# power.net
KiCad netlist of a schematic drawn in EAGLE
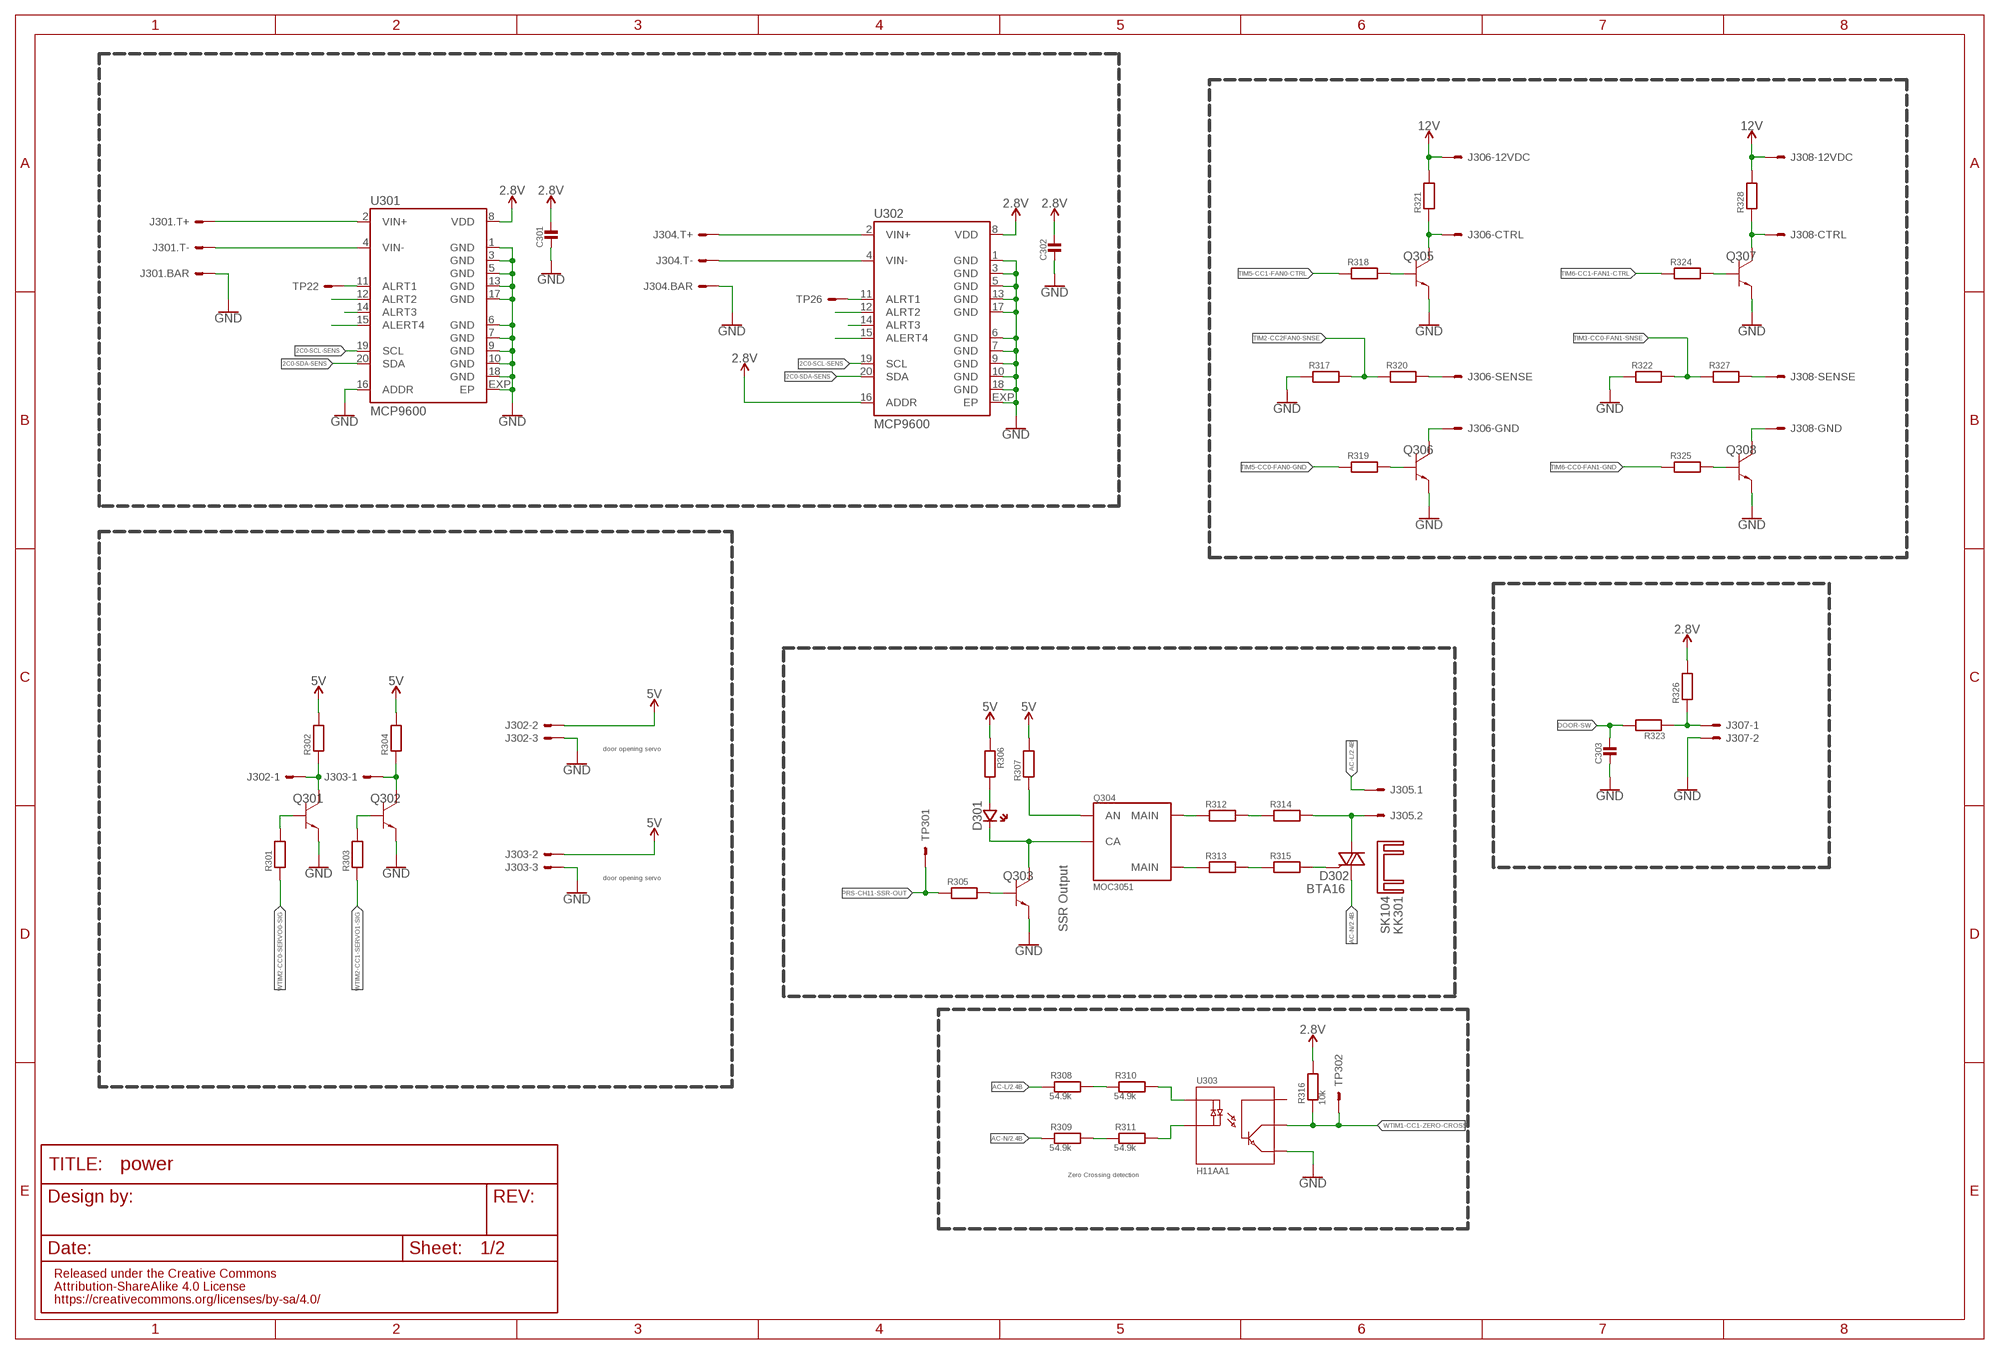
[diagram p0: schematic, sheet 1]
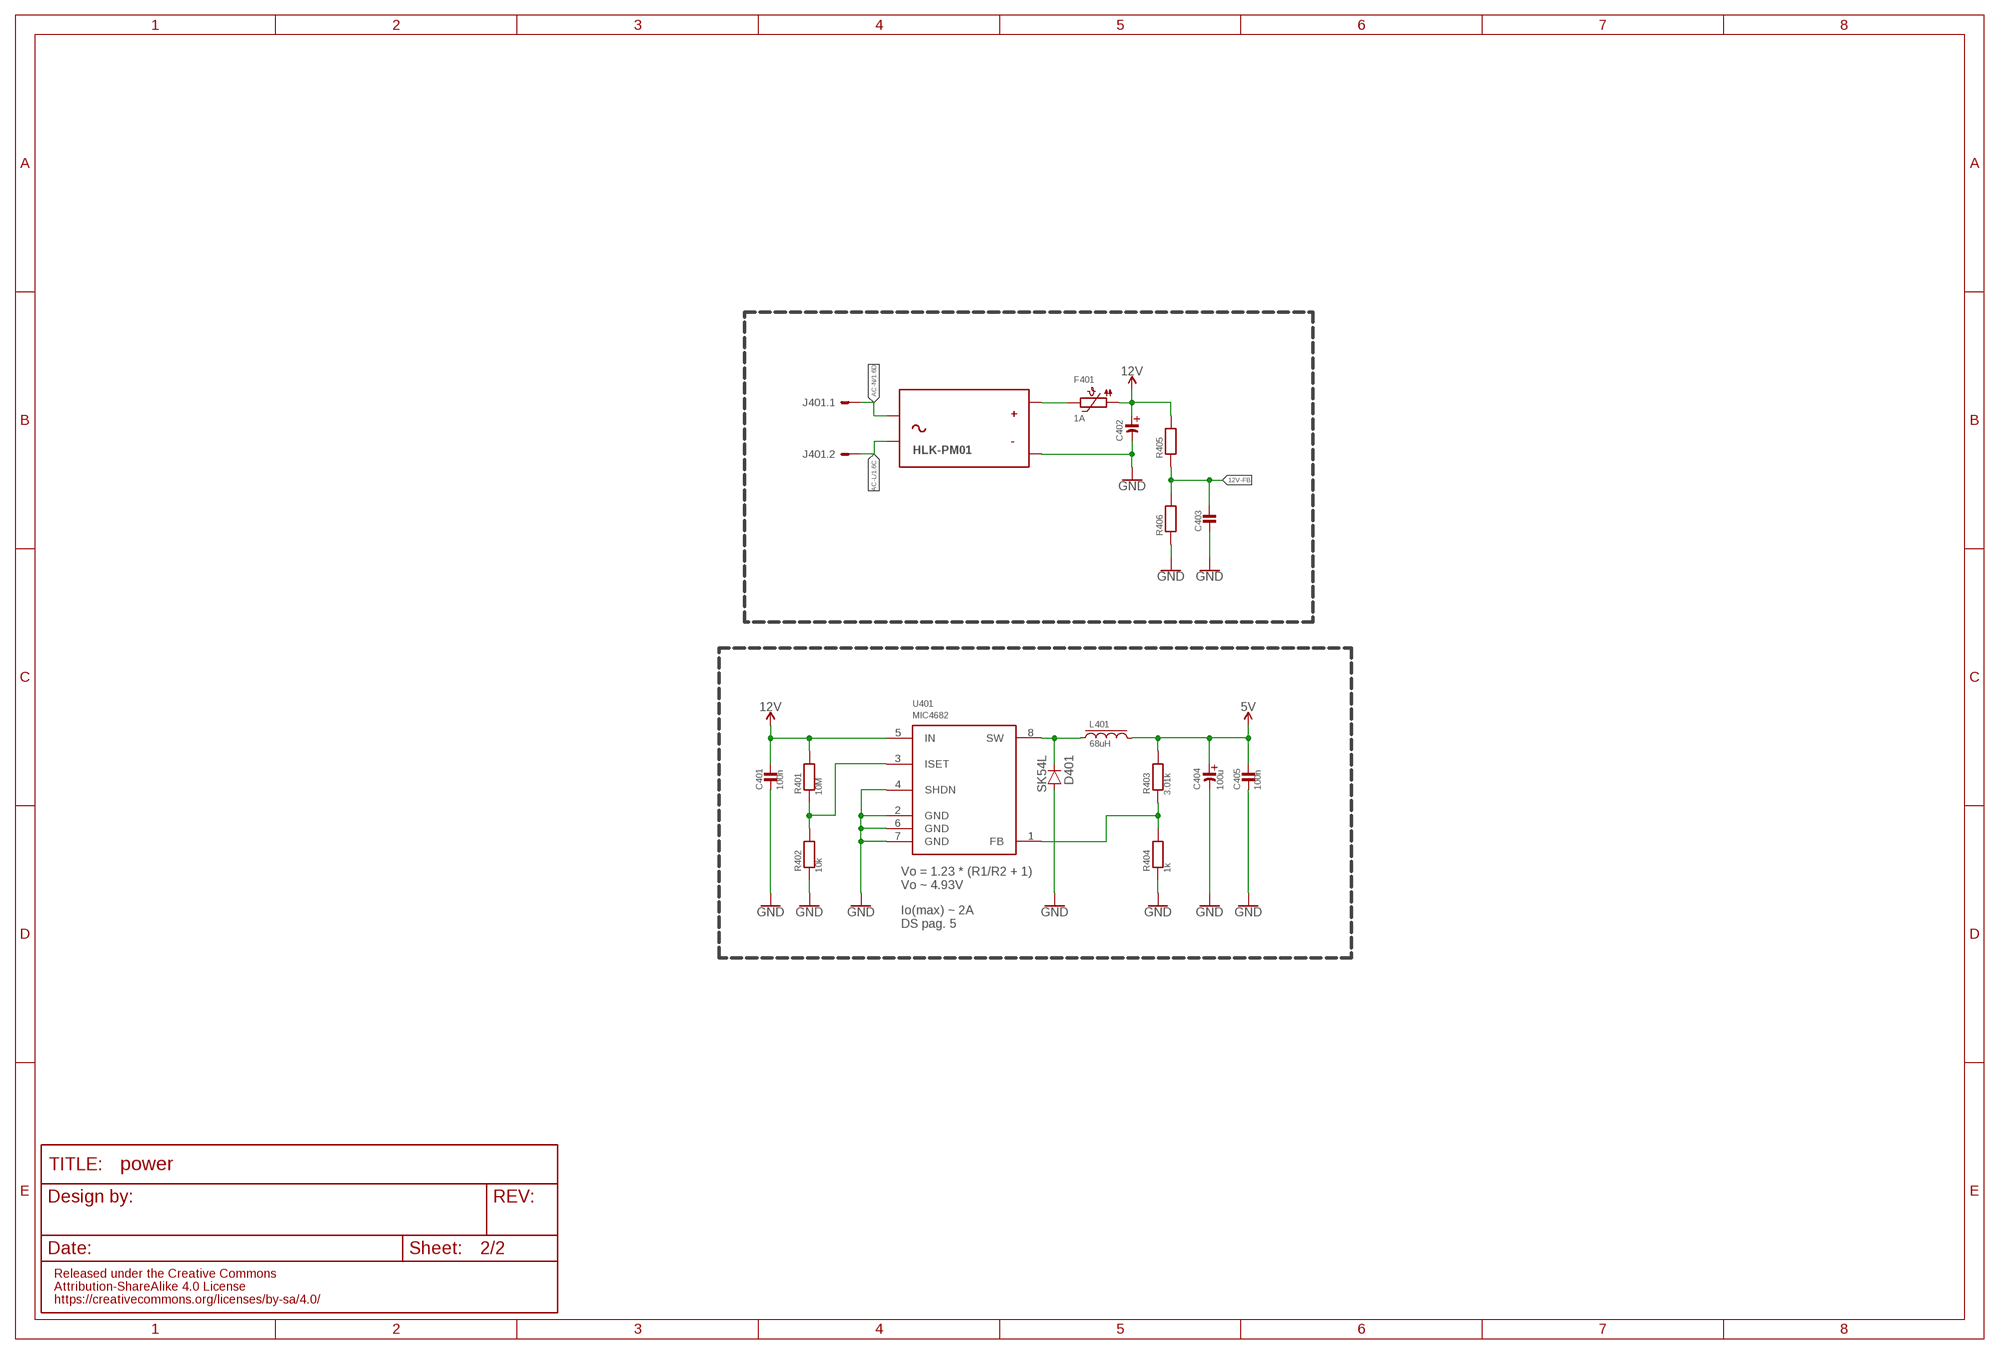
[diagram p1: schematic, sheet 2]

(export (version "E")
  (design (tool "Eeschema 10.0.6"))
  (components
    (comp (ref "C301")
      (value "MLCC0603")
      (footprint "eagle-import:0603_WAVE")
      (libsource (lib "eagle-import") (part "MLCC0603"))
    )
    (comp (ref "C302")
      (value "MLCC0603")
      (footprint "eagle-import:0603_WAVE")
      (libsource (lib "eagle-import") (part "MLCC0603"))
    )
    (comp (ref "C303")
      (value "MLCC0603")
      (footprint "eagle-import:0603_WAVE")
      (libsource (lib "eagle-import") (part "MLCC0603"))
    )
    (comp (ref "D301")
      (value "LED0603")
      (footprint "eagle-import:CHIPLED_0603")
      (libsource (lib "eagle-import") (part "LED0603"))
    )
    (comp (ref "D302")
      (value "BTA16")
      (footprint "eagle-import:TO220DS")
      (libsource (lib "eagle-import") (part "BTA16"))
    )
    (comp (ref "J301")
      (value "PCC-SMP")
      (footprint "eagle-import:PCC-SMP")
      (libsource (lib "eagle-import") (part "PCC-SMP"))
    )
    (comp (ref "J302")
      (value "3X1_2.54")
      (footprint "eagle-import:3X1_2.54")
      (libsource (lib "eagle-import") (part "3X1_2.54"))
    )
    (comp (ref "J303")
      (value "3X1_2.54")
      (footprint "eagle-import:3X1_2.54")
      (libsource (lib "eagle-import") (part "3X1_2.54"))
    )
    (comp (ref "J304")
      (value "PCC-SMP")
      (footprint "eagle-import:PCC-SMP")
      (libsource (lib "eagle-import") (part "PCC-SMP"))
    )
    (comp (ref "J305")
      (value "2EDG-2P")
      (footprint "eagle-import:2EDG-2P")
      (libsource (lib "eagle-import") (part "2EDG-2P"))
    )
    (comp (ref "J306")
      (value "4P-PC-FAN")
      (footprint "eagle-import:KF2510-3+1P")
      (libsource (lib "eagle-import") (part "4P-PC-FAN"))
    )
    (comp (ref "J307")
      (value "2X1_2.54")
      (footprint "eagle-import:2X1_2.54")
      (libsource (lib "eagle-import") (part "2X1_2.54"))
    )
    (comp (ref "J308")
      (value "4P-PC-FAN")
      (footprint "eagle-import:KF2510-3+1P")
      (libsource (lib "eagle-import") (part "4P-PC-FAN"))
    )
    (comp (ref "KK301")
      (value "SK104")
      (footprint "eagle-import:SK104")
      (libsource (lib "eagle-import") (part "SK104"))
    )
    (comp (ref "Q301")
      (value "BC817-40")
      (footprint "eagle-import:SOT-23-3")
      (libsource (lib "eagle-import") (part "BC817-40"))
    )
    (comp (ref "Q302")
      (value "BC817-40")
      (footprint "eagle-import:SOT-23-3")
      (libsource (lib "eagle-import") (part "BC817-40"))
    )
    (comp (ref "Q303")
      (value "BC817-40")
      (footprint "eagle-import:SOT-23-3")
      (libsource (lib "eagle-import") (part "BC817-40"))
    )
    (comp (ref "Q304")
      (value "MOC3051")
      (footprint "eagle-import:DIP-6-SMD")
      (libsource (lib "eagle-import") (part "MOC3051"))
    )
    (comp (ref "Q305")
      (value "BC817-40")
      (footprint "eagle-import:SOT-23-3")
      (libsource (lib "eagle-import") (part "BC817-40"))
    )
    (comp (ref "Q306")
      (value "BC817-40")
      (footprint "eagle-import:SOT-23-3")
      (libsource (lib "eagle-import") (part "BC817-40"))
    )
    (comp (ref "Q307")
      (value "BC817-40")
      (footprint "eagle-import:SOT-23-3")
      (libsource (lib "eagle-import") (part "BC817-40"))
    )
    (comp (ref "Q308")
      (value "BC817-40")
      (footprint "eagle-import:SOT-23-3")
      (libsource (lib "eagle-import") (part "BC817-40"))
    )
    (comp (ref "R301")
      (value "RESISTOR0603")
      (footprint "eagle-import:0603_WAVE")
      (libsource (lib "eagle-import") (part "RESISTOR0603"))
    )
    (comp (ref "R302")
      (value "RESISTOR0603")
      (footprint "eagle-import:0603_WAVE")
      (libsource (lib "eagle-import") (part "RESISTOR0603"))
    )
    (comp (ref "R303")
      (value "RESISTOR0603")
      (footprint "eagle-import:0603_WAVE")
      (libsource (lib "eagle-import") (part "RESISTOR0603"))
    )
    (comp (ref "R304")
      (value "RESISTOR0603")
      (footprint "eagle-import:0603_WAVE")
      (libsource (lib "eagle-import") (part "RESISTOR0603"))
    )
    (comp (ref "R305")
      (value "RESISTOR0603")
      (footprint "eagle-import:0603_WAVE")
      (libsource (lib "eagle-import") (part "RESISTOR0603"))
    )
    (comp (ref "R306")
      (value "RESISTOR0603")
      (footprint "eagle-import:0603_WAVE")
      (libsource (lib "eagle-import") (part "RESISTOR0603"))
    )
    (comp (ref "R307")
      (value "RESISTOR0603")
      (footprint "eagle-import:0603_WAVE")
      (libsource (lib "eagle-import") (part "RESISTOR0603"))
    )
    (comp (ref "R308")
      (value "54.9k")
      (footprint "eagle-import:_1206")
      (libsource (lib "eagle-import") (part "RESISTOR_1206"))
    )
    (comp (ref "R309")
      (value "54.9k")
      (footprint "eagle-import:_1206")
      (libsource (lib "eagle-import") (part "RESISTOR_1206"))
    )
    (comp (ref "R310")
      (value "54.9k")
      (footprint "eagle-import:_1206")
      (libsource (lib "eagle-import") (part "RESISTOR_1206"))
    )
    (comp (ref "R311")
      (value "54.9k")
      (footprint "eagle-import:_1206")
      (libsource (lib "eagle-import") (part "RESISTOR_1206"))
    )
    (comp (ref "R312")
      (value "RESISTOR_1206")
      (footprint "eagle-import:_1206")
      (libsource (lib "eagle-import") (part "RESISTOR_1206"))
    )
    (comp (ref "R313")
      (value "RESISTOR_1206")
      (footprint "eagle-import:_1206")
      (libsource (lib "eagle-import") (part "RESISTOR_1206"))
    )
    (comp (ref "R314")
      (value "RESISTOR_1206")
      (footprint "eagle-import:_1206")
      (libsource (lib "eagle-import") (part "RESISTOR_1206"))
    )
    (comp (ref "R315")
      (value "RESISTOR_1206")
      (footprint "eagle-import:_1206")
      (libsource (lib "eagle-import") (part "RESISTOR_1206"))
    )
    (comp (ref "R316")
      (value "10k")
      (footprint "eagle-import:0603_WAVE")
      (libsource (lib "eagle-import") (part "RESISTOR0603"))
    )
    (comp (ref "R317")
      (value "RESISTOR0603")
      (footprint "eagle-import:0603_WAVE")
      (libsource (lib "eagle-import") (part "RESISTOR0603"))
    )
    (comp (ref "R318")
      (value "RESISTOR0603")
      (footprint "eagle-import:0603_WAVE")
      (libsource (lib "eagle-import") (part "RESISTOR0603"))
    )
    (comp (ref "R319")
      (value "RESISTOR0603")
      (footprint "eagle-import:0603_WAVE")
      (libsource (lib "eagle-import") (part "RESISTOR0603"))
    )
    (comp (ref "R320")
      (value "RESISTOR0603")
      (footprint "eagle-import:0603_WAVE")
      (libsource (lib "eagle-import") (part "RESISTOR0603"))
    )
    (comp (ref "R321")
      (value "RESISTOR0603")
      (footprint "eagle-import:0603_WAVE")
      (libsource (lib "eagle-import") (part "RESISTOR0603"))
    )
    (comp (ref "R322")
      (value "RESISTOR0603")
      (footprint "eagle-import:0603_WAVE")
      (libsource (lib "eagle-import") (part "RESISTOR0603"))
    )
    (comp (ref "R323")
      (value "RESISTOR0603")
      (footprint "eagle-import:0603_WAVE")
      (libsource (lib "eagle-import") (part "RESISTOR0603"))
    )
    (comp (ref "R324")
      (value "RESISTOR0603")
      (footprint "eagle-import:0603_WAVE")
      (libsource (lib "eagle-import") (part "RESISTOR0603"))
    )
    (comp (ref "R325")
      (value "RESISTOR0603")
      (footprint "eagle-import:0603_WAVE")
      (libsource (lib "eagle-import") (part "RESISTOR0603"))
    )
    (comp (ref "R326")
      (value "RESISTOR0603")
      (footprint "eagle-import:0603_WAVE")
      (libsource (lib "eagle-import") (part "RESISTOR0603"))
    )
    (comp (ref "R327")
      (value "RESISTOR0603")
      (footprint "eagle-import:0603_WAVE")
      (libsource (lib "eagle-import") (part "RESISTOR0603"))
    )
    (comp (ref "R328")
      (value "RESISTOR0603")
      (footprint "eagle-import:0603_WAVE")
      (libsource (lib "eagle-import") (part "RESISTOR0603"))
    )
    (comp (ref "TP22")
      (value "TEST_POINT")
      (footprint "eagle-import:TEST_POINT")
      (libsource (lib "eagle-import") (part "TEST_POINT"))
    )
    (comp (ref "TP26")
      (value "TEST_POINT")
      (footprint "eagle-import:TEST_POINT")
      (libsource (lib "eagle-import") (part "TEST_POINT"))
    )
    (comp (ref "TP301")
      (value "TEST_POINT")
      (footprint "eagle-import:TEST_POINT")
      (libsource (lib "eagle-import") (part "TEST_POINT"))
    )
    (comp (ref "TP302")
      (value "TEST_POINT")
      (footprint "eagle-import:TEST_POINT")
      (libsource (lib "eagle-import") (part "TEST_POINT"))
    )
    (comp (ref "U301")
      (value "MCP9600")
      (footprint "eagle-import:TQFN20-5X5")
      (libsource (lib "eagle-import") (part "MCP9600"))
    )
    (comp (ref "U302")
      (value "MCP9600")
      (footprint "eagle-import:TQFN20-5X5")
      (libsource (lib "eagle-import") (part "MCP9600"))
    )
    (comp (ref "U303")
      (value "H11AA1")
      (footprint "eagle-import:DIP-6-SMD")
      (libsource (lib "eagle-import") (part "H11AA1"))
    )
    (comp (ref "ACDC401")
      (value "HLK-PM01")
      (footprint "eagle-import:HLK-PM01")
      (libsource (lib "eagle-import") (part "HLK-PM01"))
    )
    (comp (ref "C401")
      (value "100n")
      (footprint "eagle-import:0603_WAVE")
      (libsource (lib "eagle-import") (part "MLCC0603"))
    )
    (comp (ref "C402")
      (value "CAPACITOR_ELD")
      (footprint "eagle-import:PANASONIC_D")
      (libsource (lib "eagle-import") (part "CAPACITOR_ELD"))
    )
    (comp (ref "C403")
      (value "MLCC0603")
      (footprint "eagle-import:0603_WAVE")
      (libsource (lib "eagle-import") (part "MLCC0603"))
    )
    (comp (ref "C404")
      (value "100u")
      (footprint "eagle-import:PANASONIC_D")
      (libsource (lib "eagle-import") (part "CAPACITOR_ELD"))
    )
    (comp (ref "C405")
      (value "100n")
      (footprint "eagle-import:0603_WAVE")
      (libsource (lib "eagle-import") (part "MLCC0603"))
    )
    (comp (ref "D401")
      (value "SK54L")
      (footprint "eagle-import:DO214AA")
      (libsource (lib "eagle-import") (part "SK54L"))
    )
    (comp (ref "F401")
      (value "1A")
      (footprint "eagle-import:PTC1812")
      (libsource (lib "eagle-import") (part "PTC1812"))
    )
    (comp (ref "J401")
      (value "2EDG-2P")
      (footprint "eagle-import:2EDG-2P")
      (libsource (lib "eagle-import") (part "2EDG-2P"))
    )
    (comp (ref "L401")
      (value "68uH")
      (footprint "eagle-import:1207")
      (libsource (lib "eagle-import") (part "INDUCTOR1207"))
    )
    (comp (ref "R401")
      (value "10M")
      (footprint "eagle-import:0603_WAVE")
      (libsource (lib "eagle-import") (part "RESISTOR0603"))
    )
    (comp (ref "R402")
      (value "10k")
      (footprint "eagle-import:0603_WAVE")
      (libsource (lib "eagle-import") (part "RESISTOR0603"))
    )
    (comp (ref "R403")
      (value "3.01k")
      (footprint "eagle-import:0603_WAVE")
      (libsource (lib "eagle-import") (part "RESISTOR0603"))
    )
    (comp (ref "R404")
      (value "1k")
      (footprint "eagle-import:0603_WAVE")
      (libsource (lib "eagle-import") (part "RESISTOR0603"))
    )
    (comp (ref "R405")
      (value "RESISTOR0603")
      (footprint "eagle-import:0603_WAVE")
      (libsource (lib "eagle-import") (part "RESISTOR0603"))
    )
    (comp (ref "R406")
      (value "RESISTOR0603")
      (footprint "eagle-import:0603_WAVE")
      (libsource (lib "eagle-import") (part "RESISTOR0603"))
    )
    (comp (ref "U401")
      (value "MIC4682")
      (footprint "eagle-import:SOIC8")
      (libsource (lib "eagle-import") (part "MIC4682"))
    )
  )
  (nets
    (net (code "1") (name "2.8V") (class "Default")
      (node (ref "C301") (pin "P$1") (pinfunction "P$1_P$1") (pintype "bidirectional"))
      (node (ref "C302") (pin "P$1") (pinfunction "P$1_P$1") (pintype "bidirectional"))
      (node (ref "R316") (pin "P$2") (pinfunction "P$2_P$2") (pintype "bidirectional"))
      (node (ref "R326") (pin "P$2") (pinfunction "P$2_P$2") (pintype "bidirectional"))
      (node (ref "U301") (pin "8") (pinfunction "VDD_8") (pintype "bidirectional"))
      (node (ref "U302") (pin "16") (pinfunction "ADDR_16") (pintype "bidirectional"))
      (node (ref "U302") (pin "8") (pinfunction "VDD_8") (pintype "bidirectional"))
    )
    (net (code "2") (name "5V") (class "Default")
      (node (ref "C404") (pin "+") (pinfunction "AN_+") (pintype "bidirectional"))
      (node (ref "C405") (pin "P$1") (pinfunction "P$1_P$1") (pintype "bidirectional"))
      (node (ref "J302") (pin "P$2") (pinfunction "S_P$2") (pintype "passive"))
      (node (ref "J303") (pin "P$2") (pinfunction "S_P$2") (pintype "passive"))
      (node (ref "L401") (pin "2") (pinfunction "P$2_2") (pintype "bidirectional"))
      (node (ref "R302") (pin "P$2") (pinfunction "P$2_P$2") (pintype "bidirectional"))
      (node (ref "R304") (pin "P$2") (pinfunction "P$2_P$2") (pintype "bidirectional"))
      (node (ref "R306") (pin "P$1") (pinfunction "P$1_P$1") (pintype "bidirectional"))
      (node (ref "R307") (pin "P$2") (pinfunction "P$2_P$2") (pintype "bidirectional"))
      (node (ref "R403") (pin "P$2") (pinfunction "P$2_P$2") (pintype "bidirectional"))
    )
    (net (code "3") (name "12V") (class "Default")
      (node (ref "C401") (pin "P$1") (pinfunction "P$1_P$1") (pintype "bidirectional"))
      (node (ref "C402") (pin "+") (pinfunction "AN_+") (pintype "bidirectional"))
      (node (ref "F401") (pin "P$1") (pinfunction "1_P$1") (pintype "passive"))
      (node (ref "J306") (pin "2") (pinfunction "S_2") (pintype "passive"))
      (node (ref "J308") (pin "2") (pinfunction "S_2") (pintype "passive"))
      (node (ref "R321") (pin "P$2") (pinfunction "P$2_P$2") (pintype "bidirectional"))
      (node (ref "R328") (pin "P$2") (pinfunction "P$2_P$2") (pintype "bidirectional"))
      (node (ref "R401") (pin "P$2") (pinfunction "P$2_P$2") (pintype "bidirectional"))
      (node (ref "R405") (pin "P$2") (pinfunction "P$2_P$2") (pintype "bidirectional"))
      (node (ref "U401") (pin "5") (pinfunction "IN_5") (pintype "bidirectional"))
    )
    (net (code "4") (name "12V-FB") (class "Default")
      (node (ref "C403") (pin "P$1") (pinfunction "P$1_P$1") (pintype "bidirectional"))
      (node (ref "R405") (pin "P$1") (pinfunction "P$1_P$1") (pintype "bidirectional"))
      (node (ref "R406") (pin "P$2") (pinfunction "P$2_P$2") (pintype "bidirectional"))
    )
    (net (code "5") (name "AC-L") (class "Default")
      (node (ref "ACDC401") (pin "AC2") (pinfunction "AC2_AC2") (pintype "bidirectional"))
      (node (ref "J305") (pin "P$1") (pinfunction "S_P$1") (pintype "passive"))
      (node (ref "J401") (pin "P$2") (pinfunction "S_P$2") (pintype "passive"))
      (node (ref "R308") (pin "1") (pinfunction "P$1_1") (pintype "bidirectional"))
    )
    (net (code "6") (name "AC-N") (class "Default")
      (node (ref "ACDC401") (pin "AC1") (pinfunction "AC1_AC1") (pintype "bidirectional"))
      (node (ref "D302") (pin "A1") (pinfunction "A1_A1") (pintype "passive"))
      (node (ref "J401") (pin "P$1") (pinfunction "S_P$1") (pintype "passive"))
      (node (ref "R309") (pin "1") (pinfunction "P$1_1") (pintype "bidirectional"))
    )
    (net (code "7") (name "DOOR-SW") (class "Default")
      (node (ref "C303") (pin "P$1") (pinfunction "P$1_P$1") (pintype "bidirectional"))
      (node (ref "R323") (pin "P$2") (pinfunction "P$2_P$2") (pintype "bidirectional"))
    )
    (net (code "8") (name "GND") (class "Default")
      (node (ref "ACDC401") (pin "-VO") (pinfunction "-VO_-VO") (pintype "bidirectional"))
      (node (ref "C301") (pin "P$2") (pinfunction "P$2_P$2") (pintype "bidirectional"))
      (node (ref "C302") (pin "P$2") (pinfunction "P$2_P$2") (pintype "bidirectional"))
      (node (ref "C303") (pin "P$2") (pinfunction "P$2_P$2") (pintype "bidirectional"))
      (node (ref "C401") (pin "P$2") (pinfunction "P$2_P$2") (pintype "bidirectional"))
      (node (ref "C402") (pin "-") (pinfunction "CA_-") (pintype "bidirectional"))
      (node (ref "C403") (pin "P$2") (pinfunction "P$2_P$2") (pintype "bidirectional"))
      (node (ref "C404") (pin "-") (pinfunction "CA_-") (pintype "bidirectional"))
      (node (ref "C405") (pin "P$2") (pinfunction "P$2_P$2") (pintype "bidirectional"))
      (node (ref "D401") (pin "A") (pinfunction "A_A") (pintype "bidirectional"))
      (node (ref "J301") (pin "3-BAR") (pinfunction "S_3-BAR") (pintype "passive"))
      (node (ref "J301") (pin "4-BAR") (pinfunction "S_4-BAR") (pintype "passive"))
      (node (ref "J302") (pin "P$3") (pinfunction "S_P$3") (pintype "passive"))
      (node (ref "J303") (pin "P$3") (pinfunction "S_P$3") (pintype "passive"))
      (node (ref "J304") (pin "3-BAR") (pinfunction "S_3-BAR") (pintype "passive"))
      (node (ref "J304") (pin "4-BAR") (pinfunction "S_4-BAR") (pintype "passive"))
      (node (ref "J307") (pin "2") (pinfunction "S_2") (pintype "passive"))
      (node (ref "Q301") (pin "P$2") (pinfunction "EM2_P$2") (pintype "bidirectional"))
      (node (ref "Q302") (pin "P$2") (pinfunction "EM2_P$2") (pintype "bidirectional"))
      (node (ref "Q303") (pin "P$2") (pinfunction "EM2_P$2") (pintype "bidirectional"))
      (node (ref "Q305") (pin "P$2") (pinfunction "EM2_P$2") (pintype "bidirectional"))
      (node (ref "Q306") (pin "P$2") (pinfunction "EM2_P$2") (pintype "bidirectional"))
      (node (ref "Q307") (pin "P$2") (pinfunction "EM2_P$2") (pintype "bidirectional"))
      (node (ref "Q308") (pin "P$2") (pinfunction "EM2_P$2") (pintype "bidirectional"))
      (node (ref "R317") (pin "P$1") (pinfunction "P$1_P$1") (pintype "bidirectional"))
      (node (ref "R322") (pin "P$1") (pinfunction "P$1_P$1") (pintype "bidirectional"))
      (node (ref "R402") (pin "P$1") (pinfunction "P$1_P$1") (pintype "bidirectional"))
      (node (ref "R404") (pin "P$1") (pinfunction "P$1_P$1") (pintype "bidirectional"))
      (node (ref "R406") (pin "P$1") (pinfunction "P$1_P$1") (pintype "bidirectional"))
      (node (ref "U301") (pin "1") (pinfunction "GND_1") (pintype "bidirectional"))
      (node (ref "U301") (pin "10") (pinfunction "GND_10") (pintype "bidirectional"))
      (node (ref "U301") (pin "13") (pinfunction "GND_13") (pintype "bidirectional"))
      (node (ref "U301") (pin "16") (pinfunction "ADDR_16") (pintype "bidirectional"))
      (node (ref "U301") (pin "17") (pinfunction "GND_17") (pintype "bidirectional"))
      (node (ref "U301") (pin "18") (pinfunction "GND_18") (pintype "bidirectional"))
      (node (ref "U301") (pin "3") (pinfunction "GND_3") (pintype "bidirectional"))
      (node (ref "U301") (pin "5") (pinfunction "GND_5") (pintype "bidirectional"))
      (node (ref "U301") (pin "6") (pinfunction "GND_6") (pintype "bidirectional"))
      (node (ref "U301") (pin "7") (pinfunction "GND_7") (pintype "bidirectional"))
      (node (ref "U301") (pin "9") (pinfunction "GND_9") (pintype "bidirectional"))
      (node (ref "U301") (pin "EXP") (pinfunction "EP_EXP") (pintype "bidirectional"))
      (node (ref "U302") (pin "1") (pinfunction "GND_1") (pintype "bidirectional"))
      (node (ref "U302") (pin "10") (pinfunction "GND_10") (pintype "bidirectional"))
      (node (ref "U302") (pin "13") (pinfunction "GND_13") (pintype "bidirectional"))
      (node (ref "U302") (pin "17") (pinfunction "GND_17") (pintype "bidirectional"))
      (node (ref "U302") (pin "18") (pinfunction "GND_18") (pintype "bidirectional"))
      (node (ref "U302") (pin "3") (pinfunction "GND_3") (pintype "bidirectional"))
      (node (ref "U302") (pin "5") (pinfunction "GND_5") (pintype "bidirectional"))
      (node (ref "U302") (pin "6") (pinfunction "GND_6") (pintype "bidirectional"))
      (node (ref "U302") (pin "7") (pinfunction "GND_7") (pintype "bidirectional"))
      (node (ref "U302") (pin "9") (pinfunction "GND_9") (pintype "bidirectional"))
      (node (ref "U302") (pin "EXP") (pinfunction "EP_EXP") (pintype "bidirectional"))
      (node (ref "U303") (pin "P$4") (pinfunction "E_P$4") (pintype "bidirectional"))
      (node (ref "U401") (pin "2") (pinfunction "GND_2") (pintype "bidirectional"))
      (node (ref "U401") (pin "4") (pinfunction "SHDN_4") (pintype "bidirectional"))
      (node (ref "U401") (pin "6") (pinfunction "GND_6") (pintype "bidirectional"))
      (node (ref "U401") (pin "7") (pinfunction "GND_7") (pintype "bidirectional"))
    )
    (net (code "9") (name "I2C0-SCL-SENS") (class "Default")
      (node (ref "U301") (pin "19") (pinfunction "SCL_19") (pintype "bidirectional"))
      (node (ref "U302") (pin "19") (pinfunction "SCL_19") (pintype "bidirectional"))
    )
    (net (code "10") (name "I2C0-SDA-SENS") (class "Default")
      (node (ref "U301") (pin "20") (pinfunction "SDA_20") (pintype "bidirectional"))
      (node (ref "U302") (pin "20") (pinfunction "SDA_20") (pintype "bidirectional"))
    )
    (net (code "11") (name "Net-(D301-AN)") (class "Default")
      (node (ref "D301") (pin "A") (pinfunction "AN_A") (pintype "bidirectional"))
      (node (ref "R306") (pin "P$2") (pinfunction "P$2_P$2") (pintype "bidirectional"))
    )
    (net (code "12") (name "Net-(D301-CA)") (class "Default")
      (node (ref "D301") (pin "C") (pinfunction "CA_C") (pintype "bidirectional"))
      (node (ref "Q303") (pin "P$3") (pinfunction "C03_P$3") (pintype "bidirectional"))
      (node (ref "Q304") (pin "P$2") (pinfunction "CA_P$2") (pintype "bidirectional"))
    )
    (net (code "13") (name "Net-(F401-2)") (class "Default")
      (node (ref "ACDC401") (pin "+VO") (pinfunction "+VO_+VO") (pintype "bidirectional"))
      (node (ref "F401") (pin "P$2") (pinfunction "2_P$2") (pintype "passive"))
    )
    (net (code "14") (name "Net-(J301B-S)") (class "Default")
      (node (ref "J301") (pin "1-T+") (pinfunction "S_1-T+") (pintype "passive"))
      (node (ref "U301") (pin "2") (pinfunction "VIN+_2") (pintype "bidirectional"))
    )
    (net (code "15") (name "Net-(J301C-S)") (class "Default")
      (node (ref "J301") (pin "2-T-") (pinfunction "S_2-T-") (pintype "passive"))
      (node (ref "U301") (pin "4") (pinfunction "VIN-_4") (pintype "bidirectional"))
    )
    (net (code "16") (name "Net-(J302A-S)") (class "Default")
      (node (ref "J302") (pin "P$1") (pinfunction "S_P$1") (pintype "passive"))
      (node (ref "Q301") (pin "P$3") (pinfunction "C03_P$3") (pintype "bidirectional"))
      (node (ref "R302") (pin "P$1") (pinfunction "P$1_P$1") (pintype "bidirectional"))
    )
    (net (code "17") (name "Net-(J303A-S)") (class "Default")
      (node (ref "J303") (pin "P$1") (pinfunction "S_P$1") (pintype "passive"))
      (node (ref "Q302") (pin "P$3") (pinfunction "C03_P$3") (pintype "bidirectional"))
      (node (ref "R304") (pin "P$1") (pinfunction "P$1_P$1") (pintype "bidirectional"))
    )
    (net (code "18") (name "Net-(J304B-S)") (class "Default")
      (node (ref "J304") (pin "1-T+") (pinfunction "S_1-T+") (pintype "passive"))
      (node (ref "U302") (pin "2") (pinfunction "VIN+_2") (pintype "bidirectional"))
    )
    (net (code "19") (name "Net-(J304C-S)") (class "Default")
      (node (ref "J304") (pin "2-T-") (pinfunction "S_2-T-") (pintype "passive"))
      (node (ref "U302") (pin "4") (pinfunction "VIN-_4") (pintype "bidirectional"))
    )
    (net (code "20") (name "Net-(J305B-S)") (class "Default")
      (node (ref "D302") (pin "A2") (pinfunction "A2_A2") (pintype "passive"))
      (node (ref "J305") (pin "P$2") (pinfunction "S_P$2") (pintype "passive"))
      (node (ref "R314") (pin "2") (pinfunction "P$2_2") (pintype "bidirectional"))
    )
    (net (code "21") (name "Net-(J306B-S)") (class "Default")
      (node (ref "J306") (pin "4") (pinfunction "S_4") (pintype "passive"))
      (node (ref "Q305") (pin "P$3") (pinfunction "C03_P$3") (pintype "bidirectional"))
      (node (ref "R321") (pin "P$1") (pinfunction "P$1_P$1") (pintype "bidirectional"))
    )
    (net (code "22") (name "Net-(J306C-S)") (class "Default")
      (node (ref "J306") (pin "1") (pinfunction "S_1") (pintype "passive"))
      (node (ref "Q306") (pin "P$3") (pinfunction "C03_P$3") (pintype "bidirectional"))
    )
    (net (code "23") (name "Net-(J306D-S)") (class "Default")
      (node (ref "J306") (pin "3") (pinfunction "S_3") (pintype "passive"))
      (node (ref "R320") (pin "P$2") (pinfunction "P$2_P$2") (pintype "bidirectional"))
    )
    (net (code "24") (name "Net-(J307A-S)") (class "Default")
      (node (ref "J307") (pin "1") (pinfunction "S_1") (pintype "passive"))
      (node (ref "R323") (pin "P$1") (pinfunction "P$1_P$1") (pintype "bidirectional"))
      (node (ref "R326") (pin "P$1") (pinfunction "P$1_P$1") (pintype "bidirectional"))
    )
    (net (code "25") (name "Net-(J308B-S)") (class "Default")
      (node (ref "J308") (pin "4") (pinfunction "S_4") (pintype "passive"))
      (node (ref "Q307") (pin "P$3") (pinfunction "C03_P$3") (pintype "bidirectional"))
      (node (ref "R328") (pin "P$1") (pinfunction "P$1_P$1") (pintype "bidirectional"))
    )
    (net (code "26") (name "Net-(J308C-S)") (class "Default")
      (node (ref "J308") (pin "1") (pinfunction "S_1") (pintype "passive"))
      (node (ref "Q308") (pin "P$3") (pinfunction "C03_P$3") (pintype "bidirectional"))
    )
    (net (code "27") (name "Net-(J308D-S)") (class "Default")
      (node (ref "J308") (pin "3") (pinfunction "S_3") (pintype "passive"))
      (node (ref "R327") (pin "P$2") (pinfunction "P$2_P$2") (pintype "bidirectional"))
    )
    (net (code "28") (name "Net-(L401-P$1)") (class "Default")
      (node (ref "D401") (pin "C") (pinfunction "C_C") (pintype "bidirectional"))
      (node (ref "L401") (pin "1") (pinfunction "P$1_1") (pintype "bidirectional"))
      (node (ref "U401") (pin "8") (pinfunction "SW_8") (pintype "bidirectional"))
    )
    (net (code "29") (name "Net-(Q301-BA1)") (class "Default")
      (node (ref "Q301") (pin "P$1") (pinfunction "BA1_P$1") (pintype "bidirectional"))
      (node (ref "R301") (pin "P$2") (pinfunction "P$2_P$2") (pintype "bidirectional"))
    )
    (net (code "30") (name "Net-(Q302-BA1)") (class "Default")
      (node (ref "Q302") (pin "P$1") (pinfunction "BA1_P$1") (pintype "bidirectional"))
      (node (ref "R303") (pin "P$2") (pinfunction "P$2_P$2") (pintype "bidirectional"))
    )
    (net (code "31") (name "Net-(Q303-BA1)") (class "Default")
      (node (ref "Q303") (pin "P$1") (pinfunction "BA1_P$1") (pintype "bidirectional"))
      (node (ref "R305") (pin "P$2") (pinfunction "P$2_P$2") (pintype "bidirectional"))
    )
    (net (code "32") (name "Net-(Q304-AN)") (class "Default")
      (node (ref "Q304") (pin "P$1") (pinfunction "AN_P$1") (pintype "bidirectional"))
      (node (ref "R307") (pin "P$1") (pinfunction "P$1_P$1") (pintype "bidirectional"))
    )
    (net (code "33") (name "Net-(Q305-BA1)") (class "Default")
      (node (ref "Q305") (pin "P$1") (pinfunction "BA1_P$1") (pintype "bidirectional"))
      (node (ref "R318") (pin "P$2") (pinfunction "P$2_P$2") (pintype "bidirectional"))
    )
    (net (code "34") (name "Net-(Q306-BA1)") (class "Default")
      (node (ref "Q306") (pin "P$1") (pinfunction "BA1_P$1") (pintype "bidirectional"))
      (node (ref "R319") (pin "P$2") (pinfunction "P$2_P$2") (pintype "bidirectional"))
    )
    (net (code "35") (name "Net-(Q307-BA1)") (class "Default")
      (node (ref "Q307") (pin "P$1") (pinfunction "BA1_P$1") (pintype "bidirectional"))
      (node (ref "R324") (pin "P$2") (pinfunction "P$2_P$2") (pintype "bidirectional"))
    )
    (net (code "36") (name "Net-(Q308-BA1)") (class "Default")
      (node (ref "Q308") (pin "P$1") (pinfunction "BA1_P$1") (pintype "bidirectional"))
      (node (ref "R325") (pin "P$2") (pinfunction "P$2_P$2") (pintype "bidirectional"))
    )
    (net (code "37") (name "Net-(R308-P$2)") (class "Default")
      (node (ref "R308") (pin "2") (pinfunction "P$2_2") (pintype "bidirectional"))
      (node (ref "R310") (pin "1") (pinfunction "P$1_1") (pintype "bidirectional"))
    )
    (net (code "38") (name "Net-(R309-P$2)") (class "Default")
      (node (ref "R309") (pin "2") (pinfunction "P$2_2") (pintype "bidirectional"))
      (node (ref "R311") (pin "1") (pinfunction "P$1_1") (pintype "bidirectional"))
    )
    (net (code "39") (name "Net-(R310-P$2)") (class "Default")
      (node (ref "R310") (pin "2") (pinfunction "P$2_2") (pintype "bidirectional"))
      (node (ref "U303") (pin "P$1") (pinfunction "AC_P$1") (pintype "bidirectional"))
    )
    (net (code "40") (name "Net-(R311-P$2)") (class "Default")
      (node (ref "R311") (pin "2") (pinfunction "P$2_2") (pintype "bidirectional"))
      (node (ref "U303") (pin "P$2") (pinfunction "CA_P$2") (pintype "bidirectional"))
    )
    (net (code "41") (name "Net-(R312-P$1)") (class "Default")
      (node (ref "Q304") (pin "P$4") (pinfunction "MAIN_P$4") (pintype "bidirectional"))
      (node (ref "R312") (pin "1") (pinfunction "P$1_1") (pintype "bidirectional"))
    )
    (net (code "42") (name "Net-(R312-P$2)") (class "Default")
      (node (ref "R312") (pin "2") (pinfunction "P$2_2") (pintype "bidirectional"))
      (node (ref "R314") (pin "1") (pinfunction "P$1_1") (pintype "bidirectional"))
    )
    (net (code "43") (name "Net-(R313-P$1)") (class "Default")
      (node (ref "Q304") (pin "P$6") (pinfunction "MAIN_P$6") (pintype "bidirectional"))
      (node (ref "R313") (pin "1") (pinfunction "P$1_1") (pintype "bidirectional"))
    )
    (net (code "44") (name "Net-(R313-P$2)") (class "Default")
      (node (ref "R313") (pin "2") (pinfunction "P$2_2") (pintype "bidirectional"))
      (node (ref "R315") (pin "1") (pinfunction "P$1_1") (pintype "bidirectional"))
    )
    (net (code "45") (name "Net-(R315-P$2)") (class "Default")
      (node (ref "D302") (pin "G") (pinfunction "G_G") (pintype "passive"))
      (node (ref "R315") (pin "2") (pinfunction "P$2_2") (pintype "bidirectional"))
    )
    (net (code "46") (name "Net-(TP22-S)") (class "Default")
      (node (ref "TP22") (pin "1") (pinfunction "S_1") (pintype "passive"))
      (node (ref "U301") (pin "11") (pinfunction "ALRT1_11") (pintype "bidirectional"))
    )
    (net (code "47") (name "Net-(TP26-S)") (class "Default")
      (node (ref "TP26") (pin "1") (pinfunction "S_1") (pintype "passive"))
      (node (ref "U302") (pin "11") (pinfunction "ALRT1_11") (pintype "bidirectional"))
    )
    (net (code "48") (name "Net-(U401-FB)") (class "Default")
      (node (ref "R403") (pin "P$1") (pinfunction "P$1_P$1") (pintype "bidirectional"))
      (node (ref "R404") (pin "P$2") (pinfunction "P$2_P$2") (pintype "bidirectional"))
      (node (ref "U401") (pin "1") (pinfunction "FB_1") (pintype "bidirectional"))
    )
    (net (code "49") (name "Net-(U401-ISET)") (class "Default")
      (node (ref "R401") (pin "P$1") (pinfunction "P$1_P$1") (pintype "bidirectional"))
      (node (ref "R402") (pin "P$2") (pinfunction "P$2_P$2") (pintype "bidirectional"))
      (node (ref "U401") (pin "3") (pinfunction "ISET_3") (pintype "bidirectional"))
    )
    (net (code "50") (name "PRS-CH11-SSR-OUT") (class "Default")
      (node (ref "R305") (pin "P$1") (pinfunction "P$1_P$1") (pintype "bidirectional"))
      (node (ref "TP301") (pin "1") (pinfunction "S_1") (pintype "passive"))
    )
    (net (code "51") (name "TIM2-CC2FAN0-SNSE") (class "Default")
      (node (ref "R317") (pin "P$2") (pinfunction "P$2_P$2") (pintype "bidirectional"))
      (node (ref "R320") (pin "P$1") (pinfunction "P$1_P$1") (pintype "bidirectional"))
    )
    (net (code "52") (name "TIM3-CC0-FAN1-SNSE") (class "Default")
      (node (ref "R322") (pin "P$2") (pinfunction "P$2_P$2") (pintype "bidirectional"))
      (node (ref "R327") (pin "P$1") (pinfunction "P$1_P$1") (pintype "bidirectional"))
    )
    (net (code "53") (name "TIM5-CC0-FAN0-GND") (class "Default")
      (node (ref "R319") (pin "P$1") (pinfunction "P$1_P$1") (pintype "bidirectional"))
    )
    (net (code "54") (name "TIM5-CC1-FAN0-CTRL") (class "Default")
      (node (ref "R318") (pin "P$1") (pinfunction "P$1_P$1") (pintype "bidirectional"))
    )
    (net (code "55") (name "TIM6-CC0-FAN1-GND") (class "Default")
      (node (ref "R325") (pin "P$1") (pinfunction "P$1_P$1") (pintype "bidirectional"))
    )
    (net (code "56") (name "TIM6-CC1-FAN1-CTRL") (class "Default")
      (node (ref "R324") (pin "P$1") (pinfunction "P$1_P$1") (pintype "bidirectional"))
    )
    (net (code "57") (name "WTIM1-CC1-ZERO-CROSS") (class "Default")
      (node (ref "R316") (pin "P$1") (pinfunction "P$1_P$1") (pintype "bidirectional"))
      (node (ref "TP302") (pin "1") (pinfunction "S_1") (pintype "passive"))
      (node (ref "U303") (pin "P$5") (pinfunction "C_P$5") (pintype "bidirectional"))
    )
    (net (code "58") (name "WTIM2-CC0-SERVO0-SIG") (class "Default")
      (node (ref "R301") (pin "P$1") (pinfunction "P$1_P$1") (pintype "bidirectional"))
    )
    (net (code "59") (name "WTIM2-CC1-SERVO1-SIG") (class "Default")
      (node (ref "R303") (pin "P$1") (pinfunction "P$1_P$1") (pintype "bidirectional"))
    )
    (net (code "60") (name "unconnected-(U301-ALERT4-Pad15)") (class "Default")
      (node (ref "U301") (pin "15") (pinfunction "ALERT4_15") (pintype "bidirectional"))
    )
    (net (code "61") (name "unconnected-(U301-ALRT2-Pad12)") (class "Default")
      (node (ref "U301") (pin "12") (pinfunction "ALRT2_12") (pintype "bidirectional"))
    )
    (net (code "62") (name "unconnected-(U301-ALRT3-Pad14)") (class "Default")
      (node (ref "U301") (pin "14") (pinfunction "ALRT3_14") (pintype "bidirectional"))
    )
    (net (code "63") (name "unconnected-(U302-ALERT4-Pad15)") (class "Default")
      (node (ref "U302") (pin "15") (pinfunction "ALERT4_15") (pintype "bidirectional"))
    )
    (net (code "64") (name "unconnected-(U302-ALRT2-Pad12)") (class "Default")
      (node (ref "U302") (pin "12") (pinfunction "ALRT2_12") (pintype "bidirectional"))
    )
    (net (code "65") (name "unconnected-(U302-ALRT3-Pad14)") (class "Default")
      (node (ref "U302") (pin "14") (pinfunction "ALRT3_14") (pintype "bidirectional"))
    )
    (net (code "66") (name "unconnected-(U303-B-PadP$6)") (class "Default")
      (node (ref "U303") (pin "P$6") (pinfunction "B_P$6") (pintype "bidirectional"))
    )
  )
)
